# camera_board_V1.net
KiCad netlist of a schematic drawn in EAGLE
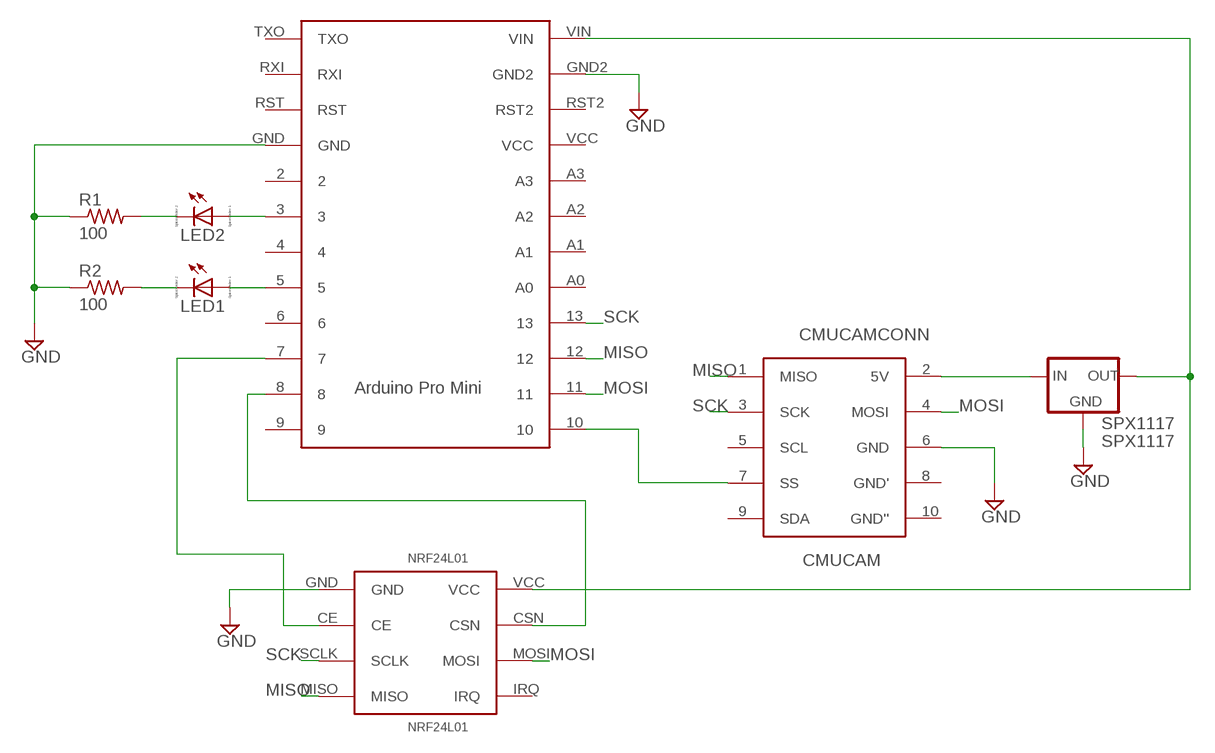
[diagram p0: schematic, sheet 1]

(export (version "E")
  (design (tool "Eeschema 10.0.6"))
  (components
    (comp (ref "ARDUINOPROMINI")
      (value "ARDUINOPROMINI")
      (footprint "eagle-import:ARDUINOPROMINI")
      (libsource (lib "eagle-import") (part "ARDUINOPROMINI"))
    )
    (comp (ref "CMUCAM")
      (value "CMUCAMCONN")
      (footprint "eagle-import:DIP10")
      (libsource (lib "eagle-import") (part "CMUCAMCONN"))
    )
    (comp (ref "LED1")
      (value "LED_E")
      (footprint "eagle-import:LED_1206")
      (libsource (lib "eagle-import") (part "LED_E"))
    )
    (comp (ref "LED2")
      (value "LED_E")
      (footprint "eagle-import:LED_1206")
      (libsource (lib "eagle-import") (part "LED_E"))
    )
    (comp (ref "NRF24L01")
      (value "NRF24L01")
      (footprint "eagle-import:DIP8")
      (libsource (lib "eagle-import") (part "NRF24L01"))
    )
    (comp (ref "R1")
      (value "100")
      (footprint "eagle-import:M1206")
      (libsource (lib "eagle-import") (part "R-US_M1206"))
    )
    (comp (ref "R2")
      (value "100")
      (footprint "eagle-import:M1206")
      (libsource (lib "eagle-import") (part "R-US_M1206"))
    )
    (comp (ref "SPX1117")
      (value "SPX1117")
      (footprint "eagle-import:SOT-223")
      (libsource (lib "eagle-import") (part "SPX1117"))
    )
  )
  (nets
    (net (code "1") (name "/MISO") (class "Default")
      (node (ref "ARDUINOPROMINI") (pin "12") (pinfunction "12_12") (pintype "bidirectional"))
      (node (ref "CMUCAM") (pin "1") (pinfunction "MISO_1") (pintype "bidirectional"))
      (node (ref "NRF24L01") (pin "MISO") (pinfunction "MISO_MISO") (pintype "bidirectional"))
    )
    (net (code "2") (name "/MOSI") (class "Default")
      (node (ref "ARDUINOPROMINI") (pin "11") (pinfunction "11_11") (pintype "bidirectional"))
      (node (ref "CMUCAM") (pin "4") (pinfunction "MOSI_4") (pintype "bidirectional"))
      (node (ref "NRF24L01") (pin "MOSI") (pinfunction "MOSI_MOSI") (pintype "bidirectional"))
    )
    (net (code "3") (name "/SCK") (class "Default")
      (node (ref "ARDUINOPROMINI") (pin "13") (pinfunction "13_13") (pintype "bidirectional"))
      (node (ref "CMUCAM") (pin "3") (pinfunction "SCK_3") (pintype "bidirectional"))
      (node (ref "NRF24L01") (pin "SCLK") (pinfunction "SCLK_SCLK") (pintype "bidirectional"))
    )
    (net (code "4") (name "GND") (class "Default")
      (node (ref "ARDUINOPROMINI") (pin "GND") (pinfunction "GND_GND") (pintype "bidirectional"))
      (node (ref "ARDUINOPROMINI") (pin "GND2") (pinfunction "GND2_GND2") (pintype "bidirectional"))
      (node (ref "CMUCAM") (pin "6") (pinfunction "GND_6") (pintype "bidirectional"))
      (node (ref "NRF24L01") (pin "GND") (pinfunction "GND_GND") (pintype "bidirectional"))
      (node (ref "R1") (pin "1") (pinfunction "1_1") (pintype "passive"))
      (node (ref "R2") (pin "1") (pinfunction "1_1") (pintype "passive"))
      (node (ref "SPX1117") (pin "1") (pinfunction "GND_1") (pintype "input"))
    )
    (net (code "5") (name "Net-(ARDUINOPROMINI-Pad3)") (class "Default")
      (node (ref "ARDUINOPROMINI") (pin "3") (pinfunction "3_3") (pintype "bidirectional"))
      (node (ref "LED2") (pin "A") (pinfunction "A_A") (pintype "passive"))
    )
    (net (code "6") (name "Net-(ARDUINOPROMINI-Pad5)") (class "Default")
      (node (ref "ARDUINOPROMINI") (pin "5") (pinfunction "5_5") (pintype "bidirectional"))
      (node (ref "LED1") (pin "A") (pinfunction "A_A") (pintype "passive"))
    )
    (net (code "7") (name "Net-(ARDUINOPROMINI-Pad7)") (class "Default")
      (node (ref "ARDUINOPROMINI") (pin "7") (pinfunction "7_7") (pintype "bidirectional"))
      (node (ref "NRF24L01") (pin "CE") (pinfunction "CE_CE") (pintype "bidirectional"))
    )
    (net (code "8") (name "Net-(ARDUINOPROMINI-Pad8)") (class "Default")
      (node (ref "ARDUINOPROMINI") (pin "8") (pinfunction "8_8") (pintype "bidirectional"))
      (node (ref "NRF24L01") (pin "CSN") (pinfunction "CSN_CSN") (pintype "bidirectional"))
    )
    (net (code "9") (name "Net-(CMUCAM-5V)") (class "Default")
      (node (ref "CMUCAM") (pin "2") (pinfunction "5V_2") (pintype "bidirectional"))
      (node (ref "SPX1117") (pin "3") (pinfunction "IN_3") (pintype "input"))
    )
    (net (code "10") (name "Net-(CMUCAM-SS)") (class "Default")
      (node (ref "ARDUINOPROMINI") (pin "10") (pinfunction "10_10") (pintype "bidirectional"))
      (node (ref "CMUCAM") (pin "7") (pinfunction "SS_7") (pintype "bidirectional"))
    )
    (net (code "11") (name "Net-(LED1-PadC)") (class "Default")
      (node (ref "LED1") (pin "C") (pinfunction "C_C") (pintype "passive"))
      (node (ref "R2") (pin "2") (pinfunction "2_2") (pintype "passive"))
    )
    (net (code "12") (name "Net-(LED2-PadC)") (class "Default")
      (node (ref "LED2") (pin "C") (pinfunction "C_C") (pintype "passive"))
      (node (ref "R1") (pin "2") (pinfunction "2_2") (pintype "passive"))
    )
    (net (code "13") (name "Net-(SPX1117-OUT)") (class "Default")
      (node (ref "ARDUINOPROMINI") (pin "VIN") (pinfunction "VIN_VIN") (pintype "bidirectional"))
      (node (ref "NRF24L01") (pin "VCC") (pinfunction "VCC_VCC") (pintype "bidirectional"))
      (node (ref "SPX1117") (pin "2") (pinfunction "OUT_2") (pintype "passive"))
    )
    (net (code "14") (name "unconnected-(ARDUINOPROMINI-Pad2)") (class "Default")
      (node (ref "ARDUINOPROMINI") (pin "2") (pinfunction "2_2") (pintype "bidirectional"))
    )
    (net (code "15") (name "unconnected-(ARDUINOPROMINI-Pad4)") (class "Default")
      (node (ref "ARDUINOPROMINI") (pin "4") (pinfunction "4_4") (pintype "bidirectional"))
    )
    (net (code "16") (name "unconnected-(ARDUINOPROMINI-Pad6)") (class "Default")
      (node (ref "ARDUINOPROMINI") (pin "6") (pinfunction "6_6") (pintype "bidirectional"))
    )
    (net (code "17") (name "unconnected-(ARDUINOPROMINI-Pad9)") (class "Default")
      (node (ref "ARDUINOPROMINI") (pin "9") (pinfunction "9_9") (pintype "bidirectional"))
    )
    (net (code "18") (name "unconnected-(ARDUINOPROMINI-PadA0)") (class "Default")
      (node (ref "ARDUINOPROMINI") (pin "A0") (pinfunction "A0_A0") (pintype "bidirectional"))
    )
    (net (code "19") (name "unconnected-(ARDUINOPROMINI-PadA1)") (class "Default")
      (node (ref "ARDUINOPROMINI") (pin "A1") (pinfunction "A1_A1") (pintype "bidirectional"))
    )
    (net (code "20") (name "unconnected-(ARDUINOPROMINI-PadA2)") (class "Default")
      (node (ref "ARDUINOPROMINI") (pin "A2") (pinfunction "A2_A2") (pintype "bidirectional"))
    )
    (net (code "21") (name "unconnected-(ARDUINOPROMINI-PadA3)") (class "Default")
      (node (ref "ARDUINOPROMINI") (pin "A3") (pinfunction "A3_A3") (pintype "bidirectional"))
    )
    (net (code "22") (name "unconnected-(ARDUINOPROMINI-PadRST)") (class "Default")
      (node (ref "ARDUINOPROMINI") (pin "RST") (pinfunction "RST_RST") (pintype "bidirectional"))
    )
    (net (code "23") (name "unconnected-(ARDUINOPROMINI-PadRST2)") (class "Default")
      (node (ref "ARDUINOPROMINI") (pin "RST2") (pinfunction "RST2_RST2") (pintype "bidirectional"))
    )
    (net (code "24") (name "unconnected-(ARDUINOPROMINI-PadRXI)") (class "Default")
      (node (ref "ARDUINOPROMINI") (pin "RXI") (pinfunction "RXI_RXI") (pintype "bidirectional"))
    )
    (net (code "25") (name "unconnected-(ARDUINOPROMINI-PadTXO)") (class "Default")
      (node (ref "ARDUINOPROMINI") (pin "TXO") (pinfunction "TXO_TXO") (pintype "bidirectional"))
    )
    (net (code "26") (name "unconnected-(ARDUINOPROMINI-PadVCC)") (class "Default")
      (node (ref "ARDUINOPROMINI") (pin "VCC") (pinfunction "VCC_VCC") (pintype "bidirectional"))
    )
    (net (code "27") (name "unconnected-(CMUCAM-GND''-Pad10)") (class "Default")
      (node (ref "CMUCAM") (pin "10") (pinfunction "GND''_10") (pintype "bidirectional"))
    )
    (net (code "28") (name "unconnected-(CMUCAM-GND'-Pad8)") (class "Default")
      (node (ref "CMUCAM") (pin "8") (pinfunction "GND'_8") (pintype "bidirectional"))
    )
    (net (code "29") (name "unconnected-(CMUCAM-SCL-Pad5)") (class "Default")
      (node (ref "CMUCAM") (pin "5") (pinfunction "SCL_5") (pintype "bidirectional"))
    )
    (net (code "30") (name "unconnected-(CMUCAM-SDA-Pad9)") (class "Default")
      (node (ref "CMUCAM") (pin "9") (pinfunction "SDA_9") (pintype "bidirectional"))
    )
    (net (code "31") (name "unconnected-(NRF24L01-PadIRQ)") (class "Default")
      (node (ref "NRF24L01") (pin "IRQ") (pinfunction "IRQ_IRQ") (pintype "bidirectional"))
    )
  )
)
